# untitled.net
KiCad netlist of a schematic drawn in EAGLE
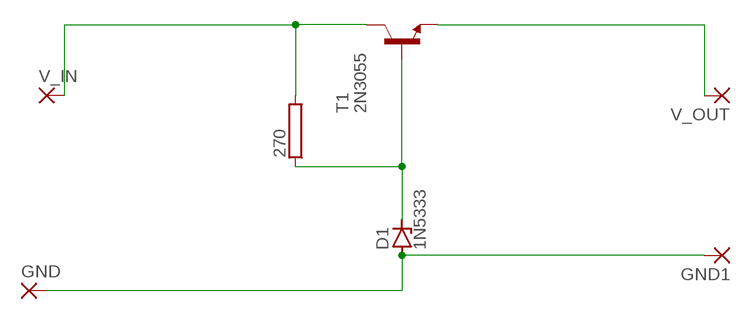
[diagram p0: schematic, sheet 1]

(export (version "E")
  (design (tool "Eeschema 10.0.6"))
  (components
    (comp (ref "270")
      (value "RMG100-V")
      (footprint "eagle-import:TO-247-2V")
      (libsource (lib "eagle-import") (part "RMG100-V"))
    )
    (comp (ref "D1")
      (value "1N5333")
      (footprint "eagle-import:C1702-15")
      (libsource (lib "eagle-import") (part "1N5333"))
    )
    (comp (ref "GND")
      (value "3,17/1,1")
      (footprint "eagle-import:3,17_1,1")
      (libsource (lib "eagle-import") (part "3,17/1,1"))
    )
    (comp (ref "GND1")
      (value "3,17/1,1")
      (footprint "eagle-import:3,17_1,1")
      (libsource (lib "eagle-import") (part "3,17/1,1"))
    )
    (comp (ref "T1")
      (value "2N3055")
      (footprint "eagle-import:TO3")
      (libsource (lib "eagle-import") (part "2N3055"))
    )
    (comp (ref "V_IN")
      (value "3,17/1,1")
      (footprint "eagle-import:3,17_1,1")
      (libsource (lib "eagle-import") (part "3,17/1,1"))
    )
    (comp (ref "V_OUT")
      (value "3,17/1,1")
      (footprint "eagle-import:3,17_1,1")
      (libsource (lib "eagle-import") (part "3,17/1,1"))
    )
  )
  (nets
    (net (code "1") (name "Net-(270-Pad1)") (class "Default")
      (node (ref "270") (pin "1") (pinfunction "1_1") (pintype "passive"))
      (node (ref "D1") (pin "C") (pinfunction "C_C") (pintype "passive"))
      (node (ref "T1") (pin "B") (pinfunction "B_B") (pintype "passive"))
    )
    (net (code "2") (name "Net-(GND-P)") (class "Default")
      (node (ref "D1") (pin "A") (pinfunction "A_A") (pintype "passive"))
      (node (ref "GND") (pin "1") (pinfunction "P_1") (pintype "passive"))
      (node (ref "GND1") (pin "1") (pinfunction "P_1") (pintype "passive"))
    )
    (net (code "3") (name "Net-(V_IN-P)") (class "Default")
      (node (ref "270") (pin "2") (pinfunction "2_2") (pintype "passive"))
      (node (ref "T1") (pin "C") (pinfunction "C_C") (pintype "passive"))
      (node (ref "T1") (pin "C/") (pinfunction "C_C/") (pintype "passive"))
      (node (ref "V_IN") (pin "1") (pinfunction "P_1") (pintype "passive"))
    )
    (net (code "4") (name "Net-(V_OUT-P)") (class "Default")
      (node (ref "T1") (pin "E") (pinfunction "E_E") (pintype "passive"))
      (node (ref "V_OUT") (pin "1") (pinfunction "P_1") (pintype "passive"))
    )
  )
)
